# EXT_TWI_LVC.net
KiCad netlist of a schematic drawn in EAGLE
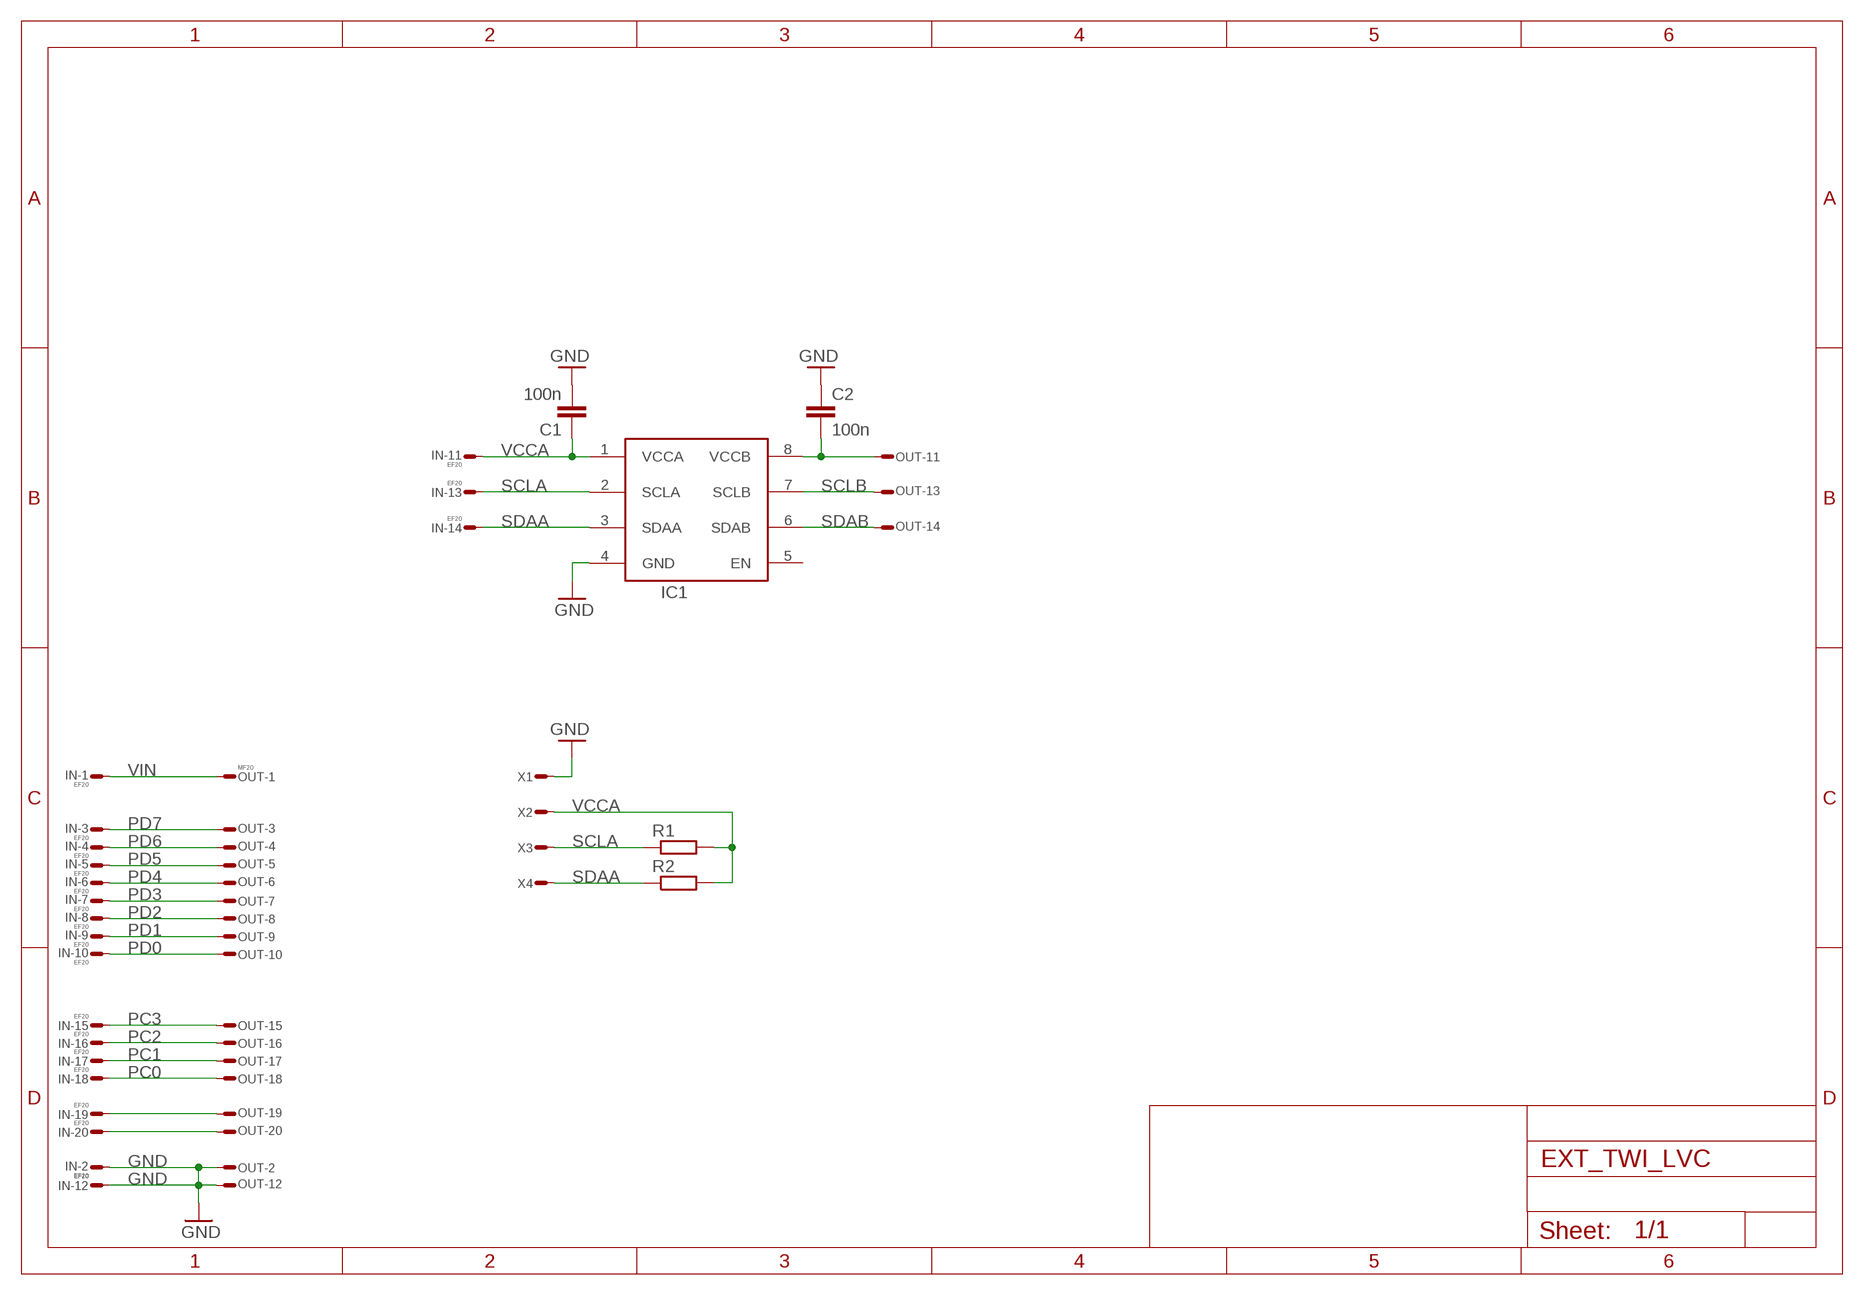
[diagram p0: schematic, sheet 1]

(export (version "E")
  (design (tool "Eeschema 10.0.6"))
  (components
    (comp (ref "C1")
      (value "100n")
      (footprint "eagle-import:0603")
      (libsource (lib "eagle-import") (part "C0603"))
    )
    (comp (ref "C2")
      (value "100n")
      (footprint "eagle-import:0603")
      (libsource (lib "eagle-import") (part "C0603"))
    )
    (comp (ref "IC1")
      (value "PCA9517D")
      (footprint "eagle-import:SOIC8")
      (libsource (lib "eagle-import") (part "PCA9517D"))
    )
    (comp (ref "IN")
      (value "EF20")
      (footprint "eagle-import:FE10-2WS")
      (libsource (lib "eagle-import") (part "FE20ELS"))
    )
    (comp (ref "OUT")
      (value "MF20")
      (footprint "eagle-import:ML20LS")
      (libsource (lib "eagle-import") (part "ML20?ELS"))
    )
    (comp (ref "R1")
      (value "R0603")
      (footprint "eagle-import:0603")
      (libsource (lib "eagle-import") (part "R0603"))
    )
    (comp (ref "R2")
      (value "R0603")
      (footprint "eagle-import:0603")
      (libsource (lib "eagle-import") (part "R0603"))
    )
    (comp (ref "X1")
      (value "WIREPADT1.6/0.9")
      (footprint "eagle-import:T1.6_0.9")
      (libsource (lib "eagle-import") (part "WIREPADT1.6/0.9"))
    )
    (comp (ref "X2")
      (value "WIREPADT1.6/0.9")
      (footprint "eagle-import:T1.6_0.9")
      (libsource (lib "eagle-import") (part "WIREPADT1.6/0.9"))
    )
    (comp (ref "X3")
      (value "WIREPADT1.6/0.9")
      (footprint "eagle-import:T1.6_0.9")
      (libsource (lib "eagle-import") (part "WIREPADT1.6/0.9"))
    )
    (comp (ref "X4")
      (value "WIREPADT1.6/0.9")
      (footprint "eagle-import:T1.6_0.9")
      (libsource (lib "eagle-import") (part "WIREPADT1.6/0.9"))
    )
  )
  (nets
    (net (code "1") (name "/PC0") (class "Default")
      (node (ref "IN") (pin "P$18") (pinfunction "S_P$18") (pintype "passive"))
      (node (ref "OUT") (pin "P$18") (pinfunction "S_P$18") (pintype "passive"))
    )
    (net (code "2") (name "/PC1") (class "Default")
      (node (ref "IN") (pin "P$17") (pinfunction "S_P$17") (pintype "passive"))
      (node (ref "OUT") (pin "P$17") (pinfunction "S_P$17") (pintype "passive"))
    )
    (net (code "3") (name "/PC2") (class "Default")
      (node (ref "IN") (pin "P$16") (pinfunction "S_P$16") (pintype "passive"))
      (node (ref "OUT") (pin "P$16") (pinfunction "S_P$16") (pintype "passive"))
    )
    (net (code "4") (name "/PC3") (class "Default")
      (node (ref "IN") (pin "P$15") (pinfunction "S_P$15") (pintype "passive"))
      (node (ref "OUT") (pin "P$15") (pinfunction "S_P$15") (pintype "passive"))
    )
    (net (code "5") (name "/PD0") (class "Default")
      (node (ref "IN") (pin "P$10") (pinfunction "S_P$10") (pintype "passive"))
      (node (ref "OUT") (pin "P$10") (pinfunction "S_P$10") (pintype "passive"))
    )
    (net (code "6") (name "/PD1") (class "Default")
      (node (ref "IN") (pin "P$9") (pinfunction "S_P$9") (pintype "passive"))
      (node (ref "OUT") (pin "P$9") (pinfunction "S_P$9") (pintype "passive"))
    )
    (net (code "7") (name "/PD2") (class "Default")
      (node (ref "IN") (pin "P$8") (pinfunction "S_P$8") (pintype "passive"))
      (node (ref "OUT") (pin "P$8") (pinfunction "S_P$8") (pintype "passive"))
    )
    (net (code "8") (name "/PD3") (class "Default")
      (node (ref "IN") (pin "P$7") (pinfunction "S_P$7") (pintype "passive"))
      (node (ref "OUT") (pin "P$7") (pinfunction "S_P$7") (pintype "passive"))
    )
    (net (code "9") (name "/PD4") (class "Default")
      (node (ref "IN") (pin "P$6") (pinfunction "S_P$6") (pintype "passive"))
      (node (ref "OUT") (pin "P$6") (pinfunction "S_P$6") (pintype "passive"))
    )
    (net (code "10") (name "/PD5") (class "Default")
      (node (ref "IN") (pin "P$5") (pinfunction "S_P$5") (pintype "passive"))
      (node (ref "OUT") (pin "P$5") (pinfunction "S_P$5") (pintype "passive"))
    )
    (net (code "11") (name "/PD6") (class "Default")
      (node (ref "IN") (pin "P$4") (pinfunction "S_P$4") (pintype "passive"))
      (node (ref "OUT") (pin "P$4") (pinfunction "S_P$4") (pintype "passive"))
    )
    (net (code "12") (name "/PD7") (class "Default")
      (node (ref "IN") (pin "P$3") (pinfunction "S_P$3") (pintype "passive"))
      (node (ref "OUT") (pin "P$3") (pinfunction "S_P$3") (pintype "passive"))
    )
    (net (code "13") (name "/SCLA") (class "Default")
      (node (ref "IC1") (pin "2") (pinfunction "SCLA_2") (pintype "bidirectional"))
      (node (ref "IN") (pin "P$13") (pinfunction "S_P$13") (pintype "passive"))
      (node (ref "R1") (pin "1") (pinfunction "1_1") (pintype "passive"))
      (node (ref "X3") (pin "1") (pinfunction "S_1") (pintype "passive"))
    )
    (net (code "14") (name "/SCLB") (class "Default")
      (node (ref "IC1") (pin "7") (pinfunction "SCLB_7") (pintype "bidirectional"))
      (node (ref "OUT") (pin "P$13") (pinfunction "S_P$13") (pintype "passive"))
    )
    (net (code "15") (name "/SDAA") (class "Default")
      (node (ref "IC1") (pin "3") (pinfunction "SDAA_3") (pintype "bidirectional"))
      (node (ref "IN") (pin "P$14") (pinfunction "S_P$14") (pintype "passive"))
      (node (ref "R2") (pin "1") (pinfunction "1_1") (pintype "passive"))
      (node (ref "X4") (pin "1") (pinfunction "S_1") (pintype "passive"))
    )
    (net (code "16") (name "/SDAB") (class "Default")
      (node (ref "IC1") (pin "6") (pinfunction "SDAB_6") (pintype "bidirectional"))
      (node (ref "OUT") (pin "P$14") (pinfunction "S_P$14") (pintype "passive"))
    )
    (net (code "17") (name "/VCCA") (class "Default")
      (node (ref "C1") (pin "1") (pinfunction "1_1") (pintype "passive"))
      (node (ref "IC1") (pin "1") (pinfunction "VCCA_1") (pintype "bidirectional"))
      (node (ref "IN") (pin "P$11") (pinfunction "S_P$11") (pintype "passive"))
      (node (ref "R1") (pin "2") (pinfunction "2_2") (pintype "passive"))
      (node (ref "R2") (pin "2") (pinfunction "2_2") (pintype "passive"))
      (node (ref "X2") (pin "1") (pinfunction "S_1") (pintype "passive"))
    )
    (net (code "18") (name "/VIN") (class "Default")
      (node (ref "IN") (pin "P$1") (pinfunction "S_P$1") (pintype "passive"))
      (node (ref "OUT") (pin "P$1") (pinfunction "S_P$1") (pintype "passive"))
    )
    (net (code "19") (name "GND") (class "Default")
      (node (ref "C1") (pin "2") (pinfunction "2_2") (pintype "passive"))
      (node (ref "C2") (pin "1") (pinfunction "1_1") (pintype "passive"))
      (node (ref "IC1") (pin "4") (pinfunction "GND_4") (pintype "bidirectional"))
      (node (ref "IN") (pin "P$12") (pinfunction "S_P$12") (pintype "passive"))
      (node (ref "IN") (pin "P$2") (pinfunction "S_P$2") (pintype "passive"))
      (node (ref "OUT") (pin "P$12") (pinfunction "S_P$12") (pintype "passive"))
      (node (ref "OUT") (pin "P$2") (pinfunction "S_P$2") (pintype "passive"))
      (node (ref "X1") (pin "1") (pinfunction "S_1") (pintype "passive"))
    )
    (net (code "20") (name "Net-(IC1-VCCB)") (class "Default")
      (node (ref "C2") (pin "2") (pinfunction "2_2") (pintype "passive"))
      (node (ref "IC1") (pin "8") (pinfunction "VCCB_8") (pintype "bidirectional"))
      (node (ref "OUT") (pin "P$11") (pinfunction "S_P$11") (pintype "passive"))
    )
    (net (code "21") (name "Net-(INK-S)") (class "Default")
      (node (ref "IN") (pin "P$19") (pinfunction "S_P$19") (pintype "passive"))
      (node (ref "OUT") (pin "P$19") (pinfunction "S_P$19") (pintype "passive"))
    )
    (net (code "22") (name "Net-(INM-S)") (class "Default")
      (node (ref "IN") (pin "P$20") (pinfunction "S_P$20") (pintype "passive"))
      (node (ref "OUT") (pin "P$20") (pinfunction "S_P$20") (pintype "passive"))
    )
    (net (code "23") (name "unconnected-(IC1-EN-Pad5)") (class "Default")
      (node (ref "IC1") (pin "5") (pinfunction "EN_5") (pintype "bidirectional"))
    )
  )
)
